# WDY_Power_Board.net
KiCad netlist of a schematic drawn in EAGLE
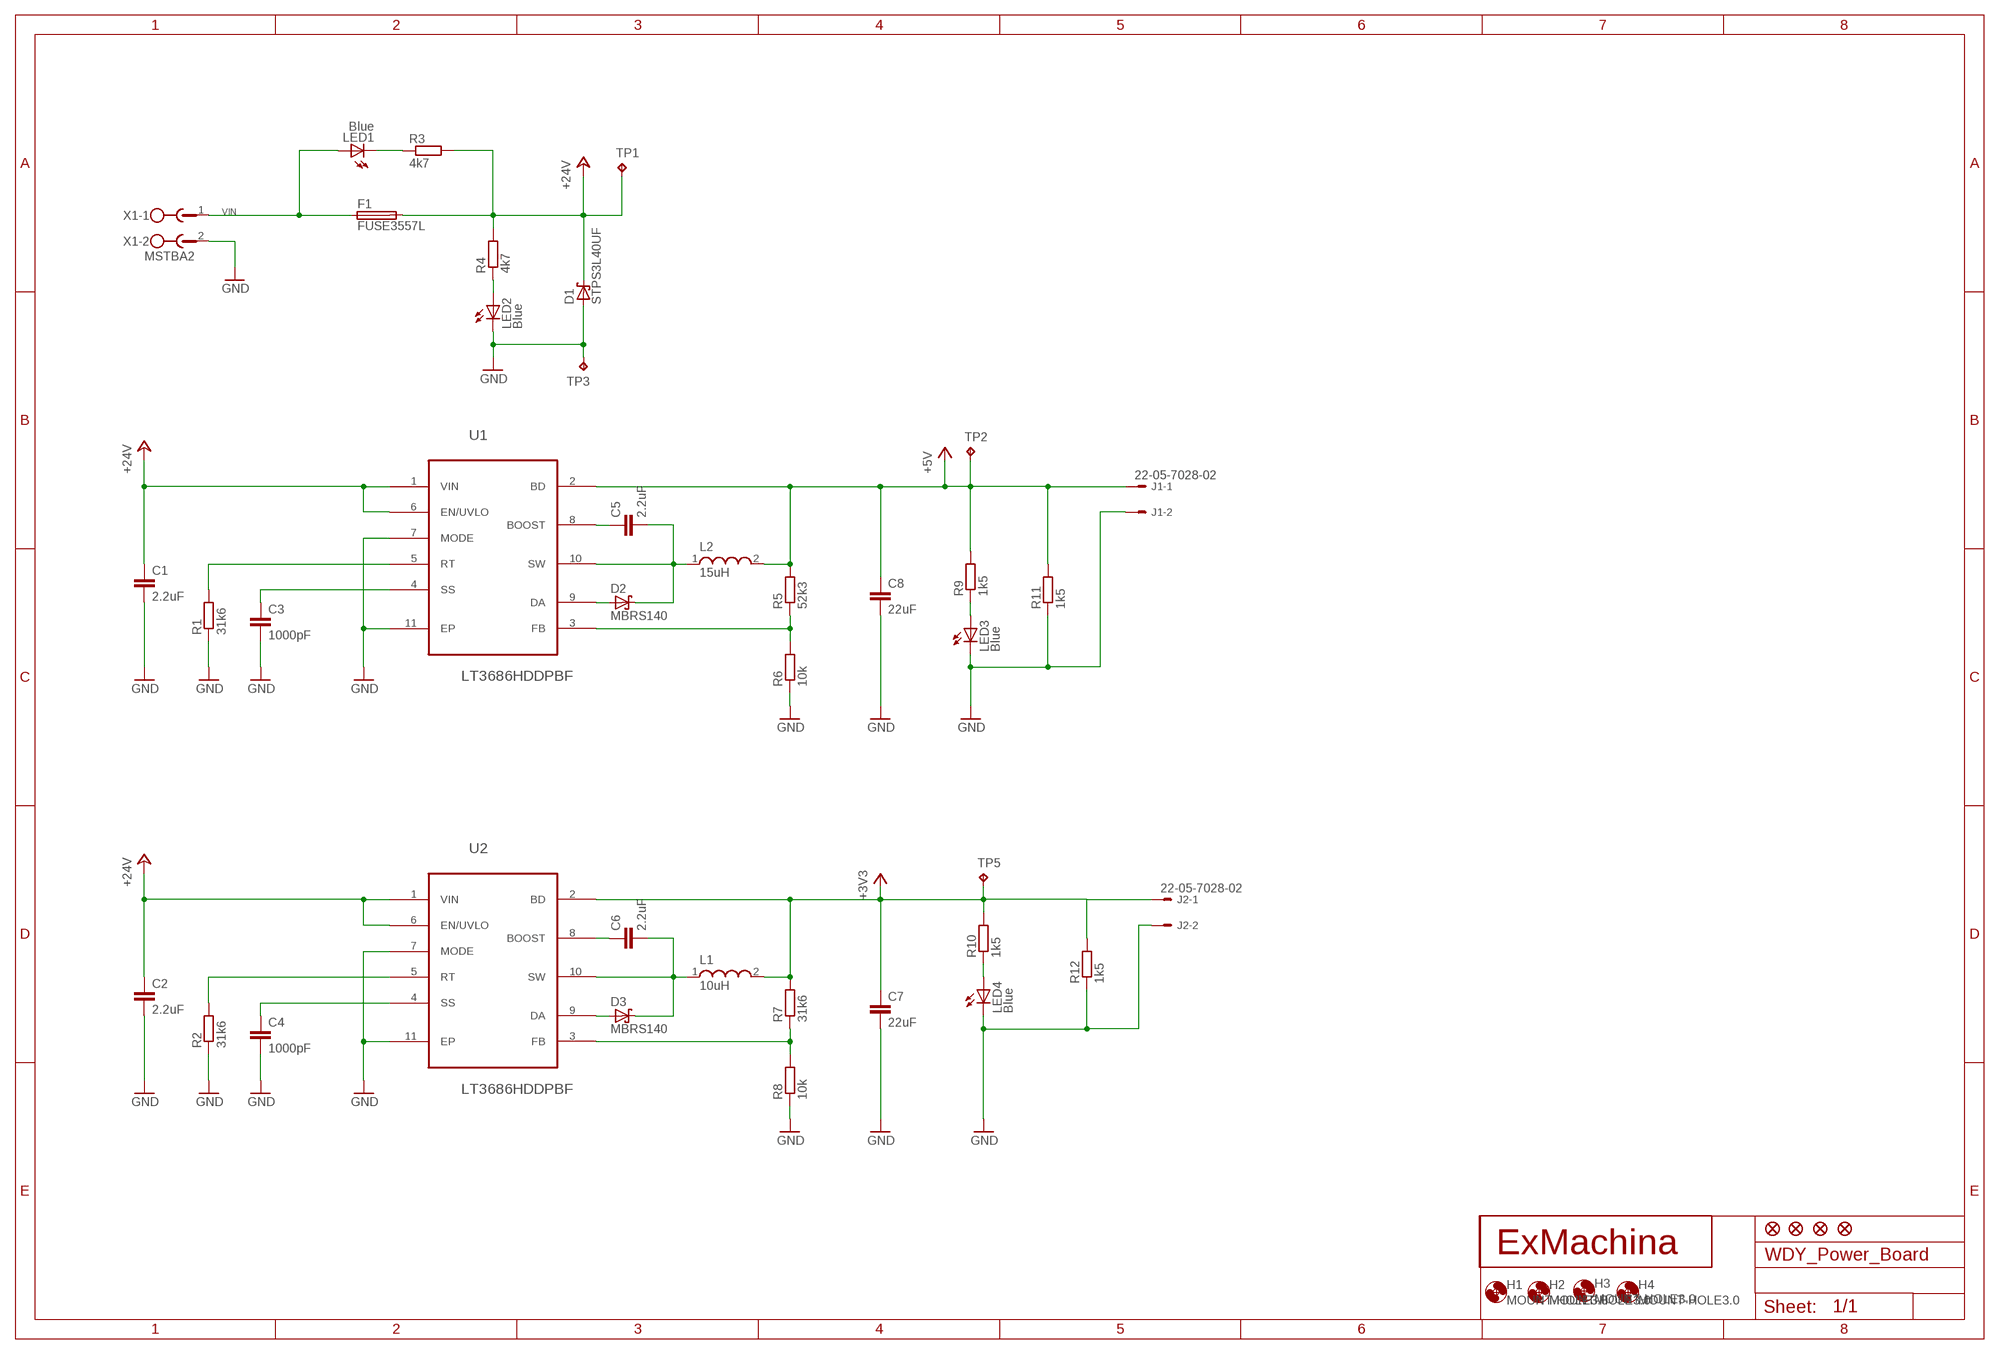
[diagram p0: schematic, sheet 1]

(export (version "E")
  (design (tool "Eeschema 10.0.6"))
  (components
    (comp (ref "C1")
      (value "2.2uF")
      (footprint "eagle-import:C0603")
      (fields (field (name "MPN") "GRT188R61H225KE13D"))
      (libsource (lib "eagle-import") (part "C-EUC0603"))
    )
    (comp (ref "C2")
      (value "2.2uF")
      (footprint "eagle-import:C0603")
      (fields (field (name "MPN") "GRT188R61H225KE13D"))
      (libsource (lib "eagle-import") (part "C-EUC0603"))
    )
    (comp (ref "C3")
      (value "1000pF")
      (footprint "eagle-import:C0603")
      (fields (field (name "MPN") "MC0603B102K500CT"))
      (libsource (lib "eagle-import") (part "C-EUC0603"))
    )
    (comp (ref "C4")
      (value "1000pF")
      (footprint "eagle-import:C0603")
      (fields (field (name "MPN") "MC0603B102K500CT"))
      (libsource (lib "eagle-import") (part "C-EUC0603"))
    )
    (comp (ref "C5")
      (value "2.2uF")
      (footprint "eagle-import:C0603")
      (fields (field (name "MPN") "GRT188R61H225KE13D"))
      (libsource (lib "eagle-import") (part "C-EUC0603"))
    )
    (comp (ref "C6")
      (value "2.2uF")
      (footprint "eagle-import:C0603")
      (fields (field (name "MPN") "GRT188R61H225KE13D"))
      (libsource (lib "eagle-import") (part "C-EUC0603"))
    )
    (comp (ref "C7")
      (value "22uF")
      (footprint "eagle-import:C0805")
      (fields (field (name "MPN") "MCMT21N220F250CT"))
      (libsource (lib "eagle-import") (part "C-EUC0805"))
    )
    (comp (ref "C8")
      (value "22uF")
      (footprint "eagle-import:C0805")
      (fields (field (name "MPN") "MCMT21N220F250CT"))
      (libsource (lib "eagle-import") (part "C-EUC0805"))
    )
    (comp (ref "D1")
      (value "STPS3L40UF")
      (footprint "eagle-import:SMB")
      (fields (field (name "MP") "STMICROELECTRONICS"))
      (libsource (lib "eagle-import") (part "STPS3L40?UF"))
    )
    (comp (ref "D2")
      (value "MBRS140")
      (footprint "eagle-import:DO-214AA")
      (fields (field (name "MF") "ON SEMICONDUCTOR") (field (name "MPN") "MBRS140T3G"))
      (libsource (lib "eagle-import") (part "MBRS140"))
    )
    (comp (ref "D3")
      (value "MBRS140")
      (footprint "eagle-import:DO-214AA")
      (fields (field (name "MF") "ON SEMICONDUCTOR") (field (name "MPN") "MBRS140T3G"))
      (libsource (lib "eagle-import") (part "MBRS140"))
    )
    (comp (ref "F1")
      (value "FUSE3557L")
      (footprint "eagle-import:3557-LITTLE")
      (fields (field (name "MPN") "3557"))
      (libsource (lib "eagle-import") (part "FUSE3557L"))
    )
    (comp (ref "H1")
      (value "MOUNT-HOLE3.0")
      (footprint "eagle-import:3,0")
      (libsource (lib "eagle-import") (part "MOUNT-HOLE3.0"))
    )
    (comp (ref "H2")
      (value "MOUNT-HOLE3.0")
      (footprint "eagle-import:3,0")
      (libsource (lib "eagle-import") (part "MOUNT-HOLE3.0"))
    )
    (comp (ref "H3")
      (value "MOUNT-HOLE3.0")
      (footprint "eagle-import:3,0")
      (libsource (lib "eagle-import") (part "MOUNT-HOLE3.0"))
    )
    (comp (ref "H4")
      (value "MOUNT-HOLE3.0")
      (footprint "eagle-import:3,0")
      (libsource (lib "eagle-import") (part "MOUNT-HOLE3.0"))
    )
    (comp (ref "J1")
      (value "22-05-7028-02")
      (footprint "eagle-import:7395-02")
      (fields (field (name "MPN") "22-05-7028") (field (name "OC_NEWARK") "25M1728"))
      (libsource (lib "eagle-import") (part "22-?-0205-7028"))
    )
    (comp (ref "J2")
      (value "22-05-7028-02")
      (footprint "eagle-import:7395-02")
      (fields (field (name "MPN") "22-05-7028") (field (name "OC_NEWARK") "25M1728"))
      (libsource (lib "eagle-import") (part "22-?-0205-7028"))
    )
    (comp (ref "JP1")
      (value "FIDUCIAL1X2")
      (footprint "eagle-import:FIDUCIAL-1X2")
      (libsource (lib "eagle-import") (part "FIDUCIAL1X2"))
    )
    (comp (ref "JP2")
      (value "FIDUCIAL1X2")
      (footprint "eagle-import:FIDUCIAL-1X2")
      (libsource (lib "eagle-import") (part "FIDUCIAL1X2"))
    )
    (comp (ref "JP3")
      (value "FIDUCIAL1X2")
      (footprint "eagle-import:FIDUCIAL-1X2")
      (libsource (lib "eagle-import") (part "FIDUCIAL1X2"))
    )
    (comp (ref "JP4")
      (value "FIDUCIAL1X2")
      (footprint "eagle-import:FIDUCIAL-1X2")
      (libsource (lib "eagle-import") (part "FIDUCIAL1X2"))
    )
    (comp (ref "L1")
      (value "10uH")
      (footprint "eagle-import:WE-PD2_5848_5820")
      (fields (field (name "MPN") "74477410"))
      (libsource (lib "eagle-import") (part "WE-PD2_5848/5820"))
    )
    (comp (ref "L2")
      (value "15uH")
      (footprint "eagle-import:WE-PD2_5848_5820")
      (fields (field (name "MPN") "744774115"))
      (libsource (lib "eagle-import") (part "WE-PD2_5848/5820"))
    )
    (comp (ref "LED1")
      (value "Blue")
      (footprint "eagle-import:CHIPLED_0603")
      (fields (field (name "MPN") "OVS-0603"))
      (libsource (lib "eagle-import") (part "LEDCHIPLED_0603"))
    )
    (comp (ref "LED2")
      (value "Blue")
      (footprint "eagle-import:CHIPLED_0603")
      (fields (field (name "MPN") "OVS-0603"))
      (libsource (lib "eagle-import") (part "LEDCHIPLED_0603"))
    )
    (comp (ref "LED3")
      (value "Blue")
      (footprint "eagle-import:CHIP-LED0603")
      (fields (field (name "MPN") "OVS-0604"))
      (libsource (lib "eagle-import") (part "LEDCHIP-LED0603"))
    )
    (comp (ref "LED4")
      (value "Blue")
      (footprint "eagle-import:CHIP-LED0603")
      (fields (field (name "MPN") "OVS-0604"))
      (libsource (lib "eagle-import") (part "LEDCHIP-LED0603"))
    )
    (comp (ref "R1")
      (value "31k6")
      (footprint "eagle-import:R0603")
      (fields (field (name "MF") "Multicomp Passives") (field (name "MPN") "MC0063W060311K5"))
      (libsource (lib "eagle-import") (part "R-EU_R0603"))
    )
    (comp (ref "R2")
      (value "31k6")
      (footprint "eagle-import:R0603")
      (fields (field (name "MF") "Multicomp Passives") (field (name "MPN") "MC0063W060311K5"))
      (libsource (lib "eagle-import") (part "R-EU_R0603"))
    )
    (comp (ref "R3")
      (value "4k7")
      (footprint "eagle-import:R0603")
      (fields (field (name "MPN") "MCMR06X4701FTL"))
      (libsource (lib "eagle-import") (part "R-EU_R0603"))
    )
    (comp (ref "R4")
      (value "4k7")
      (footprint "eagle-import:R0603")
      (fields (field (name "MPN") "MCMR06X4701FTL"))
      (libsource (lib "eagle-import") (part "R-EU_R0603"))
    )
    (comp (ref "R5")
      (value "52k3")
      (footprint "eagle-import:R0603")
      (fields (field (name "MPN") "MC0063W0603152K3"))
      (libsource (lib "eagle-import") (part "R-EU_R0603"))
    )
    (comp (ref "R6")
      (value "10k")
      (footprint "eagle-import:R0603")
      (fields (field (name "MPN") "MCMR06X1002FTL"))
      (libsource (lib "eagle-import") (part "R-EU_R0603"))
    )
    (comp (ref "R7")
      (value "31k6")
      (footprint "eagle-import:R0603")
      (fields (field (name "MF") "Multicomp Passives") (field (name "MPN") "MC0063W060311K5"))
      (libsource (lib "eagle-import") (part "R-EU_R0603"))
    )
    (comp (ref "R8")
      (value "10k")
      (footprint "eagle-import:R0603")
      (fields (field (name "MPN") "MCMR06X1002FTL"))
      (libsource (lib "eagle-import") (part "R-EU_R0603"))
    )
    (comp (ref "R9")
      (value "1k5")
      (footprint "eagle-import:R0603")
      (fields (field (name "MF") "Multicomp Passives") (field (name "MPN") "MC0063W060311K5"))
      (libsource (lib "eagle-import") (part "R-EU_R0603"))
    )
    (comp (ref "R10")
      (value "1k5")
      (footprint "eagle-import:R0603")
      (fields (field (name "MF") "Multicomp Passives") (field (name "MPN") "MC0063W060311K5"))
      (libsource (lib "eagle-import") (part "R-EU_R0603"))
    )
    (comp (ref "R11")
      (value "1k5")
      (footprint "eagle-import:R0603")
      (fields (field (name "MF") "Multicomp Passives") (field (name "MPN") "MC0063W060311K5"))
      (libsource (lib "eagle-import") (part "R-EU_R0603"))
    )
    (comp (ref "R12")
      (value "1k5")
      (footprint "eagle-import:R0603")
      (fields (field (name "MF") "Multicomp Passives") (field (name "MPN") "MC0063W060311K5"))
      (libsource (lib "eagle-import") (part "R-EU_R0603"))
    )
    (comp (ref "TP1")
      (value "TPB1,27")
      (footprint "eagle-import:B1,27")
      (libsource (lib "eagle-import") (part "TPB1,27"))
    )
    (comp (ref "TP2")
      (value "TPB1,27")
      (footprint "eagle-import:B1,27")
      (libsource (lib "eagle-import") (part "TPB1,27"))
    )
    (comp (ref "TP3")
      (value "TPB1,27")
      (footprint "eagle-import:B1,27")
      (libsource (lib "eagle-import") (part "TPB1,27"))
    )
    (comp (ref "TP5")
      (value "TPB1,27")
      (footprint "eagle-import:B1,27")
      (libsource (lib "eagle-import") (part "TPB1,27"))
    )
    (comp (ref "U$1")
      (value "EXMACHINA-LOGO-NAME")
      (footprint "eagle-import:EXM-LOGO-BASELINE")
      (libsource (lib "eagle-import") (part "EXMACHINA-LOGO-NAME"))
    )
    (comp (ref "U1")
      (value "LT3686HDDPBF")
      (footprint "eagle-import:DFN300X300X80-11N")
      (fields (field (name "MPN") "LT3686HDD#PBF"))
      (libsource (lib "eagle-import") (part "LT3686HDDPBF"))
    )
    (comp (ref "U2")
      (value "LT3686HDDPBF")
      (footprint "eagle-import:DFN300X300X80-11N")
      (fields (field (name "MPN") "LT3686HDD#PBF"))
      (libsource (lib "eagle-import") (part "LT3686HDDPBF"))
    )
    (comp (ref "X1")
      (value "MSTBA2")
      (footprint "eagle-import:MSTBA2")
      (fields (field (name "MF") "FARNELL") (field (name "MPN") "1757242"))
      (libsource (lib "eagle-import") (part "MSTBA2"))
    )
  )
  (nets
    (net (code "1") (name "+3V3") (class "Default")
      (node (ref "C7") (pin "1") (pinfunction "1_1") (pintype "passive"))
      (node (ref "J2") (pin "1") (pinfunction "S_1") (pintype "passive"))
      (node (ref "L1") (pin "2") (pinfunction "2_2") (pintype "passive"))
      (node (ref "R10") (pin "2") (pinfunction "2_2") (pintype "passive"))
      (node (ref "R12") (pin "2") (pinfunction "2_2") (pintype "passive"))
      (node (ref "R7") (pin "2") (pinfunction "2_2") (pintype "passive"))
      (node (ref "TP5") (pin "TP") (pinfunction "TP_TP") (pintype "input"))
      (node (ref "U2") (pin "2") (pinfunction "BD_2") (pintype "input"))
    )
    (net (code "2") (name "+5V") (class "Default")
      (node (ref "C8") (pin "1") (pinfunction "1_1") (pintype "passive"))
      (node (ref "J1") (pin "1") (pinfunction "S_1") (pintype "passive"))
      (node (ref "L2") (pin "2") (pinfunction "2_2") (pintype "passive"))
      (node (ref "R11") (pin "2") (pinfunction "2_2") (pintype "passive"))
      (node (ref "R5") (pin "2") (pinfunction "2_2") (pintype "passive"))
      (node (ref "R9") (pin "2") (pinfunction "2_2") (pintype "passive"))
      (node (ref "TP2") (pin "TP") (pinfunction "TP_TP") (pintype "input"))
      (node (ref "U1") (pin "2") (pinfunction "BD_2") (pintype "input"))
    )
    (net (code "3") (name "+24V") (class "Default")
      (node (ref "C1") (pin "1") (pinfunction "1_1") (pintype "passive"))
      (node (ref "C2") (pin "1") (pinfunction "1_1") (pintype "passive"))
      (node (ref "D1") (pin "C") (pinfunction "C_C") (pintype "passive"))
      (node (ref "F1") (pin "3") (pinfunction "2_3") (pintype "passive"))
      (node (ref "F1") (pin "4") (pinfunction "2_4") (pintype "passive"))
      (node (ref "R3") (pin "2") (pinfunction "2_2") (pintype "passive"))
      (node (ref "R4") (pin "2") (pinfunction "2_2") (pintype "passive"))
      (node (ref "TP1") (pin "TP") (pinfunction "TP_TP") (pintype "input"))
      (node (ref "U1") (pin "1") (pinfunction "VIN_1") (pintype "power_in"))
      (node (ref "U1") (pin "6") (pinfunction "EN/UVLO_6") (pintype "input"))
      (node (ref "U2") (pin "1") (pinfunction "VIN_1") (pintype "power_in"))
      (node (ref "U2") (pin "6") (pinfunction "EN/UVLO_6") (pintype "input"))
    )
    (net (code "4") (name "/VIN") (class "Default")
      (node (ref "F1") (pin "1") (pinfunction "1_1") (pintype "passive"))
      (node (ref "F1") (pin "2") (pinfunction "1_2") (pintype "passive"))
      (node (ref "LED1") (pin "A") (pinfunction "A_A") (pintype "passive"))
      (node (ref "X1") (pin "1") (pinfunction "1_1") (pintype "passive"))
    )
    (net (code "5") (name "GND") (class "Default")
      (node (ref "C1") (pin "2") (pinfunction "2_2") (pintype "passive"))
      (node (ref "C2") (pin "2") (pinfunction "2_2") (pintype "passive"))
      (node (ref "C3") (pin "2") (pinfunction "2_2") (pintype "passive"))
      (node (ref "C4") (pin "2") (pinfunction "2_2") (pintype "passive"))
      (node (ref "C7") (pin "2") (pinfunction "2_2") (pintype "passive"))
      (node (ref "C8") (pin "2") (pinfunction "2_2") (pintype "passive"))
      (node (ref "D1") (pin "A") (pinfunction "A_A") (pintype "passive"))
      (node (ref "J1") (pin "2") (pinfunction "S_2") (pintype "passive"))
      (node (ref "J2") (pin "2") (pinfunction "S_2") (pintype "passive"))
      (node (ref "LED2") (pin "C") (pinfunction "C_C") (pintype "passive"))
      (node (ref "LED3") (pin "C") (pinfunction "C_C") (pintype "passive"))
      (node (ref "LED4") (pin "C") (pinfunction "C_C") (pintype "passive"))
      (node (ref "R1") (pin "1") (pinfunction "1_1") (pintype "passive"))
      (node (ref "R11") (pin "1") (pinfunction "1_1") (pintype "passive"))
      (node (ref "R12") (pin "1") (pinfunction "1_1") (pintype "passive"))
      (node (ref "R2") (pin "1") (pinfunction "1_1") (pintype "passive"))
      (node (ref "R6") (pin "1") (pinfunction "1_1") (pintype "passive"))
      (node (ref "R8") (pin "1") (pinfunction "1_1") (pintype "passive"))
      (node (ref "TP3") (pin "TP") (pinfunction "TP_TP") (pintype "input"))
      (node (ref "U1") (pin "11") (pinfunction "EP_11") (pintype "passive"))
      (node (ref "U1") (pin "7") (pinfunction "MODE_7") (pintype "input"))
      (node (ref "U2") (pin "11") (pinfunction "EP_11") (pintype "passive"))
      (node (ref "U2") (pin "7") (pinfunction "MODE_7") (pintype "input"))
      (node (ref "X1") (pin "2") (pinfunction "1_2") (pintype "passive"))
    )
    (net (code "6") (name "Net-(LED1-PadC)") (class "Default")
      (node (ref "LED1") (pin "C") (pinfunction "C_C") (pintype "passive"))
      (node (ref "R3") (pin "1") (pinfunction "1_1") (pintype "passive"))
    )
    (net (code "7") (name "Net-(LED2-PadA)") (class "Default")
      (node (ref "LED2") (pin "A") (pinfunction "A_A") (pintype "passive"))
      (node (ref "R4") (pin "1") (pinfunction "1_1") (pintype "passive"))
    )
    (net (code "8") (name "Net-(LED3-PadA)") (class "Default")
      (node (ref "LED3") (pin "A") (pinfunction "A_A") (pintype "passive"))
      (node (ref "R9") (pin "1") (pinfunction "1_1") (pintype "passive"))
    )
    (net (code "9") (name "Net-(LED4-PadA)") (class "Default")
      (node (ref "LED4") (pin "A") (pinfunction "A_A") (pintype "passive"))
      (node (ref "R10") (pin "1") (pinfunction "1_1") (pintype "passive"))
    )
    (net (code "10") (name "Net-(U1-BOOST)") (class "Default")
      (node (ref "C5") (pin "1") (pinfunction "1_1") (pintype "passive"))
      (node (ref "U1") (pin "8") (pinfunction "BOOST_8") (pintype "power_in"))
    )
    (net (code "11") (name "Net-(U1-DA)") (class "Default")
      (node (ref "D2") (pin "A") (pinfunction "A_A") (pintype "passive"))
      (node (ref "U1") (pin "9") (pinfunction "DA_9") (pintype "input"))
    )
    (net (code "12") (name "Net-(U1-FB)") (class "Default")
      (node (ref "R5") (pin "1") (pinfunction "1_1") (pintype "passive"))
      (node (ref "R6") (pin "2") (pinfunction "2_2") (pintype "passive"))
      (node (ref "U1") (pin "3") (pinfunction "FB_3") (pintype "input"))
    )
    (net (code "13") (name "Net-(U1-RT)") (class "Default")
      (node (ref "R1") (pin "2") (pinfunction "2_2") (pintype "passive"))
      (node (ref "U1") (pin "5") (pinfunction "RT_5") (pintype "input"))
    )
    (net (code "14") (name "Net-(U1-SS)") (class "Default")
      (node (ref "C3") (pin "1") (pinfunction "1_1") (pintype "passive"))
      (node (ref "U1") (pin "4") (pinfunction "SS_4") (pintype "input"))
    )
    (net (code "15") (name "Net-(U1-SW)") (class "Default")
      (node (ref "C5") (pin "2") (pinfunction "2_2") (pintype "passive"))
      (node (ref "D2") (pin "C") (pinfunction "C_C") (pintype "passive"))
      (node (ref "L2") (pin "1") (pinfunction "1_1") (pintype "passive"))
      (node (ref "U1") (pin "10") (pinfunction "SW_10") (pintype "output"))
    )
    (net (code "16") (name "Net-(U2-BOOST)") (class "Default")
      (node (ref "C6") (pin "1") (pinfunction "1_1") (pintype "passive"))
      (node (ref "U2") (pin "8") (pinfunction "BOOST_8") (pintype "power_in"))
    )
    (net (code "17") (name "Net-(U2-DA)") (class "Default")
      (node (ref "D3") (pin "A") (pinfunction "A_A") (pintype "passive"))
      (node (ref "U2") (pin "9") (pinfunction "DA_9") (pintype "input"))
    )
    (net (code "18") (name "Net-(U2-FB)") (class "Default")
      (node (ref "R7") (pin "1") (pinfunction "1_1") (pintype "passive"))
      (node (ref "R8") (pin "2") (pinfunction "2_2") (pintype "passive"))
      (node (ref "U2") (pin "3") (pinfunction "FB_3") (pintype "input"))
    )
    (net (code "19") (name "Net-(U2-RT)") (class "Default")
      (node (ref "R2") (pin "2") (pinfunction "2_2") (pintype "passive"))
      (node (ref "U2") (pin "5") (pinfunction "RT_5") (pintype "input"))
    )
    (net (code "20") (name "Net-(U2-SS)") (class "Default")
      (node (ref "C4") (pin "1") (pinfunction "1_1") (pintype "passive"))
      (node (ref "U2") (pin "4") (pinfunction "SS_4") (pintype "input"))
    )
    (net (code "21") (name "Net-(U2-SW)") (class "Default")
      (node (ref "C6") (pin "2") (pinfunction "2_2") (pintype "passive"))
      (node (ref "D3") (pin "C") (pinfunction "C_C") (pintype "passive"))
      (node (ref "L1") (pin "1") (pinfunction "1_1") (pintype "passive"))
      (node (ref "U2") (pin "10") (pinfunction "SW_10") (pintype "output"))
    )
  )
)
